# USB_FS.net
KiCad netlist of a schematic drawn in Altium Designer
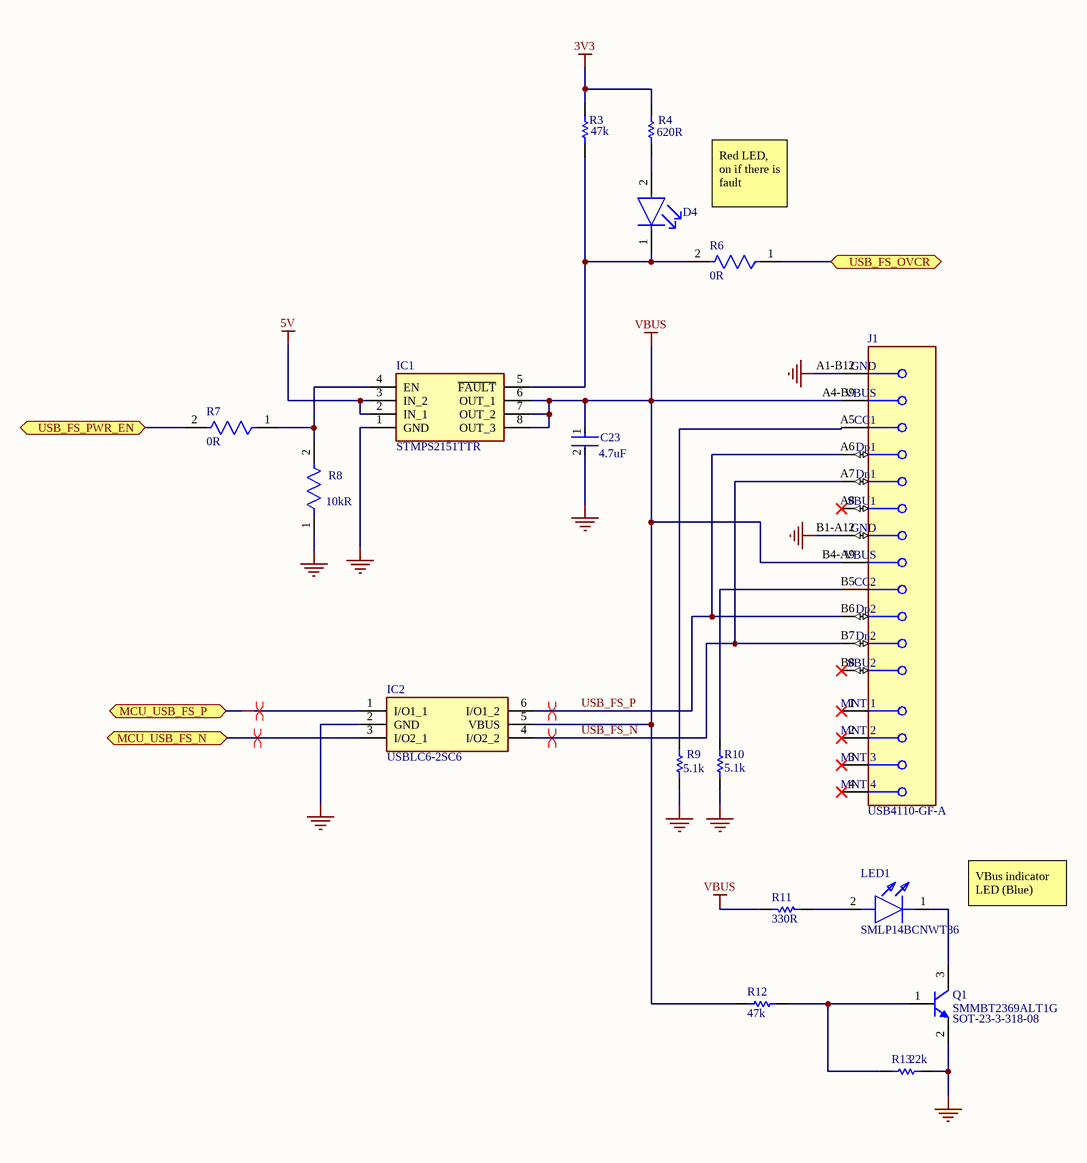
[diagram p0: USB_FS.SchDoc]

(export (version "E")
  (design (tool "Eeschema 10.0.6"))
  (components
    (comp (ref "C23")
      (value "GCM21BC71A475KA73K")
      (footprint "FP-GCM21B-0_15-IPC_B")
      (description "Ceramic Capacitor for Automotive 4.7uF ±10% 10VDC X7S 0805 Embossed T/R")
      (fields (field (name "CAPACITANCE") "4.7uF") (field (name "TOLERANCE") "10%"))
      (libsource (lib "Altium Content Vault") (part "02cd4be3c70576c341d710602a673aa"))
    )
    (comp (ref "D4")
      (value "SML-P11UTT86R")
      (footprint "FP-SML-P1-MFG")
      (description "LED RED CLEAR 1006 SMD")
      (fields
        (field (name "MANUFACTURER") "Rohm")
        (field (name "OCTOPART") "https://octopart.com/sml-p11utt86r-rohm-39058751")
      )
      (libsource (lib "Altium Content Vault") (part "8706943c75ba83719d021d2fdc84c58"))
    )
    (comp (ref "IC1")
      (value "STMPS2151TTR")
      (footprint "SamacSys:SOP65P490X110-8N")
      (description "Integrated Circuit")
      (fields (field (name "MOUSER PART NUMBER") "511-STMPS2151TTR"))
      (libsource (lib "*") (part "STMPS2151TTR"))
    )
    (comp (ref "IC2")
      (value "USBLC6-2SC6")
      (footprint "SamacSys:SOT95P280X145-6N")
      (description "Integrated Circuit")
      (fields (field (name "MOUSER PART NUMBER") "511-USBLC6-2SC6"))
      (libsource (lib "*") (part "USBLC6-2SC6"))
    )
    (comp (ref "J1")
      (value "USB4110-GF-A")
      (footprint "FP-USB4110-GF-A-MFG")
      (description "CONN USB 2.0 TYPE-C R/A SMT")
      (fields
        (field (name "OCTOPART") "https://octopart.com/usb4110-gf-a-gct-103941985")
        (field (name "MANUFACTURER") "GCT")
      )
      (libsource (lib "Altium Content Vault") (part "e23f2b38bb3c3f98e683ebab9ede730"))
    )
    (comp (ref "LED1")
      (value "SMLP14BCNWT86")
      (footprint "SamacSys:SMLP14BCNWT86")
      (description "LED")
      (libsource (lib "*") (part "SMLP14BCNWT86"))
    )
    (comp (ref "Q1")
      (value "SMMBT2369ALT1G")
      (footprint "ONSC-SOT-23-3-318-08_V")
      (description "Switching Transistor, NPN Silicon, 3-Pin SOT-23, Pb-Free, Tape and Reel")
      (fields
        (field (name "PACKAGEREFERENCE") "SOT-23-3-318-08")
        (field (name "MANUFACTURER") "On Semiconductor")
      )
      (libsource (lib "Altium Content Vault") (part "ONSC-NPN-B1E2C3-3"))
    )
    (comp (ref "R3")
      (value "RC0402JR-0747KL")
      (footprint "RESC1005X40X25LL05T10")
      (fields (field (name "MANUFACTURER") "Yageo / Phycomp") (field (name "RESISTANCE") "47k"))
      (libsource (lib "Altium Content Vault") (part "RES"))
    )
    (comp (ref "R4")
      (value "RC0402JR-07620RL")
      (footprint "RESC1005X40X25ML05T10")
      (fields (field (name "MANUFACTURER") "Yageo / Phycomp") (field (name "RESISTANCE") "620R"))
      (libsource (lib "Altium Content Vault") (part "RES"))
    )
    (comp (ref "R6")
      (value "RMCF0402ZT0R00")
      (footprint "FP-RMCF0402-MFG")
      (description "RES 0 OHM JUMPER 1/16W 0402")
      (fields (field (name "RESISTANCE") "0R"))
      (libsource (lib "Altium Content Vault") (part "1029c3af85768c4190bb7ad29bc67b5"))
    )
    (comp (ref "R7")
      (value "RMCF0402ZT0R00")
      (footprint "FP-RMCF0402-MFG")
      (description "RES 0 OHM JUMPER 1/16W 0402")
      (fields (field (name "RESISTANCE") "0R"))
      (libsource (lib "Altium Content Vault") (part "1029c3af85768c4190bb7ad29bc67b5"))
    )
    (comp (ref "R8")
      (value "RC0402FR-1310KL")
      (footprint "FP-RC0402-0_4-IPC_A")
      (description "RESISTOR 0402 10K 1%")
      (fields (field (name "RESISTANCE") "10kR") (field (name "TOLERANCE") "1%"))
      (libsource (lib "Altium Content Vault") (part "1029c3af85768c4190bb7ad29bc67b5"))
    )
    (comp (ref "R9")
      (value "RC0402JR-0751KL")
      (footprint "RESC1005X40X25ML05T10")
      (fields (field (name "MANUFACTURER") "Yageo / Phycomp") (field (name "RESISTANCE") "5.1k"))
      (libsource (lib "Altium Content Vault") (part "RES"))
    )
    (comp (ref "R10")
      (value "RC0402JR-0751KL")
      (footprint "RESC1005X40X25ML05T10")
      (fields (field (name "MANUFACTURER") "Yageo / Phycomp") (field (name "RESISTANCE") "5.1k"))
      (libsource (lib "Altium Content Vault") (part "RES"))
    )
    (comp (ref "R11")
      (value "RC0402JR-07330RL")
      (footprint "RESC1005X40X25NL05T10")
      (fields (field (name "MANUFACTURER") "Yageo / Phycomp") (field (name "PARAMETER") "330R"))
      (libsource (lib "Altium Content Vault") (part "RES"))
    )
    (comp (ref "R12")
      (value "RC0402JR-0747KL")
      (footprint "RESC1005X40X25LL05T10")
      (fields (field (name "MANUFACTURER") "Yageo / Phycomp") (field (name "RESISTANCE") "47k"))
      (libsource (lib "Altium Content Vault") (part "RES"))
    )
    (comp (ref "R13")
      (value "RC0402FR-07422KL")
      (footprint "RESC1005X40X25NL05T10")
      (fields (field (name "MANUFACTURER") "Yageo") (field (name "RESISTANCE") "22k"))
      (libsource (lib "Altium Content Vault") (part "RES"))
    )
  )
  (nets
    (net (code "1") (name "/MCU_USB_FS_N") (class "Default")
      (node (ref "IC2") (pin "3") (pinfunction "I/O2_1_3") (pintype "passive"))
    )
    (net (code "2") (name "/MCU_USB_FS_P") (class "Default")
      (node (ref "IC2") (pin "1") (pinfunction "I/O1_1_1") (pintype "passive"))
    )
    (net (code "3") (name "/USB_FS_N") (class "Default")
      (node (ref "IC2") (pin "4") (pinfunction "I/O2_2_4") (pintype "passive"))
      (node (ref "J1") (pin "A7") (pinfunction "Dn1_A7") (pintype "bidirectional"))
      (node (ref "J1") (pin "B7") (pinfunction "Dn2_B7") (pintype "bidirectional"))
    )
    (net (code "4") (name "/USB_FS_OVCR") (class "Default")
      (node (ref "R6") (pin "1") (pinfunction "1_1") (pintype "passive"))
    )
    (net (code "5") (name "/USB_FS_P") (class "Default")
      (node (ref "IC2") (pin "6") (pinfunction "I/O1_2_6") (pintype "passive"))
      (node (ref "J1") (pin "A6") (pinfunction "Dp1_A6") (pintype "bidirectional"))
      (node (ref "J1") (pin "B6") (pinfunction "Dp2_B6") (pintype "bidirectional"))
    )
    (net (code "6") (name "/USB_FS_PWR_EN") (class "Default")
      (node (ref "R7") (pin "2") (pinfunction "2_2") (pintype "passive"))
    )
    (net (code "7") (name "3V3") (class "Default")
      (node (ref "R3") (pin "2") (pinfunction "2_2") (pintype "passive"))
      (node (ref "R4") (pin "2") (pinfunction "2_2") (pintype "passive"))
    )
    (net (code "8") (name "5V") (class "Default")
      (node (ref "IC1") (pin "2") (pinfunction "IN_1_2") (pintype "passive"))
      (node (ref "IC1") (pin "3") (pinfunction "IN_2_3") (pintype "passive"))
    )
    (net (code "9") (name "GND") (class "Default")
      (node (ref "C23") (pin "2") (pinfunction "2_2") (pintype "passive"))
      (node (ref "IC1") (pin "1") (pinfunction "GND_1") (pintype "passive"))
      (node (ref "IC2") (pin "2") (pinfunction "GND_2") (pintype "passive"))
      (node (ref "J1") (pin "A1-B12") (pinfunction "GND_A1-B12") (pintype "passive"))
      (node (ref "J1") (pin "B1-A12") (pinfunction "GND_B1-A12") (pintype "bidirectional"))
      (node (ref "Q1") (pin "2") (pinfunction "E_2") (pintype "passive"))
      (node (ref "R10") (pin "1") (pinfunction "1_1") (pintype "passive"))
      (node (ref "R13") (pin "2") (pinfunction "2_2") (pintype "passive"))
      (node (ref "R8") (pin "1") (pinfunction "1_1") (pintype "passive"))
      (node (ref "R9") (pin "1") (pinfunction "1_1") (pintype "passive"))
    )
    (net (code "10") (name "Net-(D4-A)") (class "Default")
      (node (ref "D4") (pin "2") (pinfunction "A_2") (pintype "passive"))
      (node (ref "R4") (pin "1") (pinfunction "1_1") (pintype "passive"))
    )
    (net (code "11") (name "Net-(D4-C)") (class "Default")
      (node (ref "D4") (pin "1") (pinfunction "C_1") (pintype "passive"))
      (node (ref "IC1") (pin "5") (pinfunction "~{FAULT}_5") (pintype "passive"))
      (node (ref "R3") (pin "1") (pinfunction "1_1") (pintype "passive"))
      (node (ref "R6") (pin "2") (pinfunction "2_2") (pintype "passive"))
    )
    (net (code "12") (name "Net-(IC1-EN)") (class "Default")
      (node (ref "IC1") (pin "4") (pinfunction "EN_4") (pintype "passive"))
      (node (ref "R7") (pin "1") (pinfunction "1_1") (pintype "passive"))
      (node (ref "R8") (pin "2") (pinfunction "2_2") (pintype "passive"))
    )
    (net (code "13") (name "Net-(J1-CC1)") (class "Default")
      (node (ref "J1") (pin "A5") (pinfunction "CC1_A5") (pintype "power_in"))
      (node (ref "R9") (pin "2") (pinfunction "2_2") (pintype "passive"))
    )
    (net (code "14") (name "Net-(J1-CC2)") (class "Default")
      (node (ref "J1") (pin "B5") (pinfunction "CC2_B5") (pintype "power_in"))
      (node (ref "R10") (pin "2") (pinfunction "2_2") (pintype "passive"))
    )
    (net (code "15") (name "Net-(LED1-A)") (class "Default")
      (node (ref "LED1") (pin "2") (pinfunction "A_2") (pintype "passive"))
      (node (ref "R11") (pin "2") (pinfunction "2_2") (pintype "passive"))
    )
    (net (code "16") (name "Net-(LED1-K)") (class "Default")
      (node (ref "LED1") (pin "1") (pinfunction "K_1") (pintype "passive"))
      (node (ref "Q1") (pin "3") (pinfunction "C_3") (pintype "passive"))
    )
    (net (code "17") (name "Net-(Q1-B)") (class "Default")
      (node (ref "Q1") (pin "1") (pinfunction "B_1") (pintype "passive"))
      (node (ref "R12") (pin "1") (pinfunction "1_1") (pintype "passive"))
      (node (ref "R13") (pin "1") (pinfunction "1_1") (pintype "passive"))
    )
    (net (code "18") (name "VBUS") (class "Default")
      (node (ref "C23") (pin "1") (pinfunction "1_1") (pintype "passive"))
      (node (ref "IC1") (pin "6") (pinfunction "OUT_1_6") (pintype "passive"))
      (node (ref "IC1") (pin "7") (pinfunction "OUT_2_7") (pintype "passive"))
      (node (ref "IC1") (pin "8") (pinfunction "OUT_3_8") (pintype "passive"))
      (node (ref "IC2") (pin "5") (pinfunction "VBUS_5") (pintype "passive"))
      (node (ref "J1") (pin "A4-B9") (pinfunction "VBUS_A4-B9") (pintype "power_in"))
      (node (ref "J1") (pin "B4-A9") (pinfunction "VBUS_B4-A9") (pintype "power_in"))
      (node (ref "R11") (pin "1") (pinfunction "1_1") (pintype "passive"))
      (node (ref "R12") (pin "2") (pinfunction "2_2") (pintype "passive"))
    )
    (net (code "19") (name "unconnected-(J1-MNT_1-Pad1)") (class "Default")
      (node (ref "J1") (pin "1") (pinfunction "MNT_1_1") (pintype "passive+no_connect"))
    )
    (net (code "20") (name "unconnected-(J1-MNT_2-Pad2)") (class "Default")
      (node (ref "J1") (pin "2") (pinfunction "MNT_2_2") (pintype "passive+no_connect"))
    )
    (net (code "21") (name "unconnected-(J1-MNT_3-Pad3)") (class "Default")
      (node (ref "J1") (pin "3") (pinfunction "MNT_3_3") (pintype "passive+no_connect"))
    )
    (net (code "22") (name "unconnected-(J1-MNT_4-Pad4)") (class "Default")
      (node (ref "J1") (pin "4") (pinfunction "MNT_4_4") (pintype "passive+no_connect"))
    )
    (net (code "23") (name "unconnected-(J1-SBU1-PadA8)") (class "Default")
      (node (ref "J1") (pin "A8") (pinfunction "SBU1_A8") (pintype "bidirectional+no_connect"))
    )
    (net (code "24") (name "unconnected-(J1-SBU2-PadB8)") (class "Default")
      (node (ref "J1") (pin "B8") (pinfunction "SBU2_B8") (pintype "bidirectional+no_connect"))
    )
  )
)
